# Pixie85.net
KiCad netlist of a schematic drawn in EAGLE
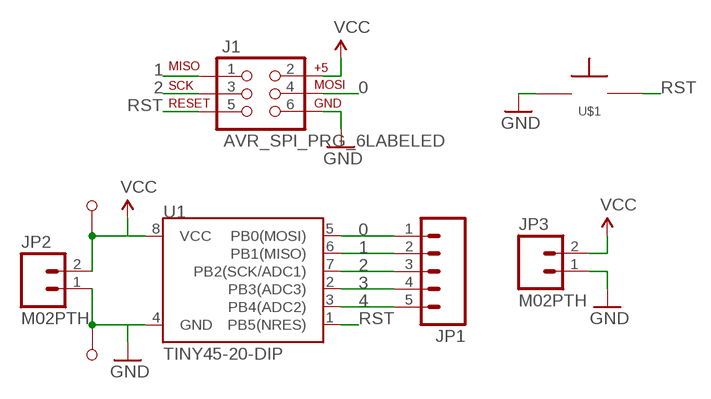
[diagram p0: schematic, sheet 1]

(export (version "E")
  (design (tool "Eeschema 10.0.6"))
  (components
    (comp (ref "+")
      (value "M1")
      (footprint "eagle-import:M1_NO_STRAIN")
      (libsource (lib "eagle-import") (part "M1"))
    )
    (comp (ref "-")
      (value "M1")
      (footprint "eagle-import:M1_NO_STRAIN")
      (libsource (lib "eagle-import") (part "M1"))
    )
    (comp (ref "J1")
      (value "AVR_SPI_PRG_6LABELED")
      (footprint "eagle-import:2X3-NS")
      (libsource (lib "eagle-import") (part "AVR_SPI_PRG_6LABELED"))
    )
    (comp (ref "JP1")
      (value "M05PTH")
      (footprint "eagle-import:1X05")
      (libsource (lib "eagle-import") (part "M05PTH"))
    )
    (comp (ref "JP2")
      (value "M02PTH")
      (footprint "eagle-import:1X02")
      (libsource (lib "eagle-import") (part "M02PTH"))
    )
    (comp (ref "JP3")
      (value "M02PTH")
      (footprint "eagle-import:1X02")
      (libsource (lib "eagle-import") (part "M02PTH"))
    )
    (comp (ref "U$1")
      (value "TAC_SPST_NO")
      (footprint "eagle-import:TAC_SPST_NO")
      (libsource (lib "eagle-import") (part "TAC_SPST_NO"))
    )
    (comp (ref "U1")
      (value "TINY45-20-DIP")
      (footprint "eagle-import:DIP08")
      (libsource (lib "eagle-import") (part "ATTINY45TINY45-20-DIP"))
    )
  )
  (nets
    (net (code "1") (name "/0") (class "Default")
      (node (ref "J1") (pin "4") (pinfunction "MOSI_4") (pintype "passive"))
      (node (ref "JP1") (pin "1") (pinfunction "1_1") (pintype "passive"))
      (node (ref "U1") (pin "5") (pinfunction "PB0(MOSI)_5") (pintype "bidirectional"))
    )
    (net (code "2") (name "/1") (class "Default")
      (node (ref "J1") (pin "1") (pinfunction "MISO_1") (pintype "passive"))
      (node (ref "JP1") (pin "2") (pinfunction "2_2") (pintype "passive"))
      (node (ref "U1") (pin "6") (pinfunction "PB1(MISO)_6") (pintype "bidirectional"))
    )
    (net (code "3") (name "/2") (class "Default")
      (node (ref "J1") (pin "3") (pinfunction "SCK_3") (pintype "passive"))
      (node (ref "JP1") (pin "3") (pinfunction "3_3") (pintype "passive"))
      (node (ref "U1") (pin "7") (pinfunction "PB2(SCK/ADC1)_7") (pintype "bidirectional"))
    )
    (net (code "4") (name "/3") (class "Default")
      (node (ref "JP1") (pin "4") (pinfunction "4_4") (pintype "passive"))
      (node (ref "U1") (pin "2") (pinfunction "PB3(ADC3)_2") (pintype "bidirectional"))
    )
    (net (code "5") (name "/4") (class "Default")
      (node (ref "JP1") (pin "5") (pinfunction "5_5") (pintype "passive"))
      (node (ref "U1") (pin "3") (pinfunction "PB4(ADC2)_3") (pintype "bidirectional"))
    )
    (net (code "6") (name "/RST") (class "Default")
      (node (ref "J1") (pin "5") (pinfunction "RST_5") (pintype "passive"))
      (node (ref "U$1") (pin "P$2") (pinfunction "P$2_P$2") (pintype "bidirectional"))
      (node (ref "U1") (pin "1") (pinfunction "PB5(NRES)_1") (pintype "bidirectional"))
    )
    (net (code "7") (name "GND") (class "Default")
      (node (ref "-") (pin "P$1") (pinfunction "P$1_P$1") (pintype "bidirectional"))
      (node (ref "J1") (pin "6") (pinfunction "GND_6") (pintype "passive"))
      (node (ref "JP2") (pin "1") (pinfunction "1_1") (pintype "passive"))
      (node (ref "JP3") (pin "1") (pinfunction "1_1") (pintype "passive"))
      (node (ref "U$1") (pin "P$1") (pinfunction "P$1_P$1") (pintype "bidirectional"))
      (node (ref "U1") (pin "4") (pinfunction "GND_4") (pintype "bidirectional"))
    )
    (net (code "8") (name "VCC") (class "Default")
      (node (ref "+") (pin "P$1") (pinfunction "P$1_P$1") (pintype "bidirectional"))
      (node (ref "J1") (pin "2") (pinfunction "V+_2") (pintype "passive"))
      (node (ref "JP2") (pin "2") (pinfunction "2_2") (pintype "passive"))
      (node (ref "JP3") (pin "2") (pinfunction "2_2") (pintype "passive"))
      (node (ref "U1") (pin "8") (pinfunction "VCC_8") (pintype "bidirectional"))
    )
  )
)
